# deca_pcb.net
KiCad netlist of a schematic drawn in EAGLE
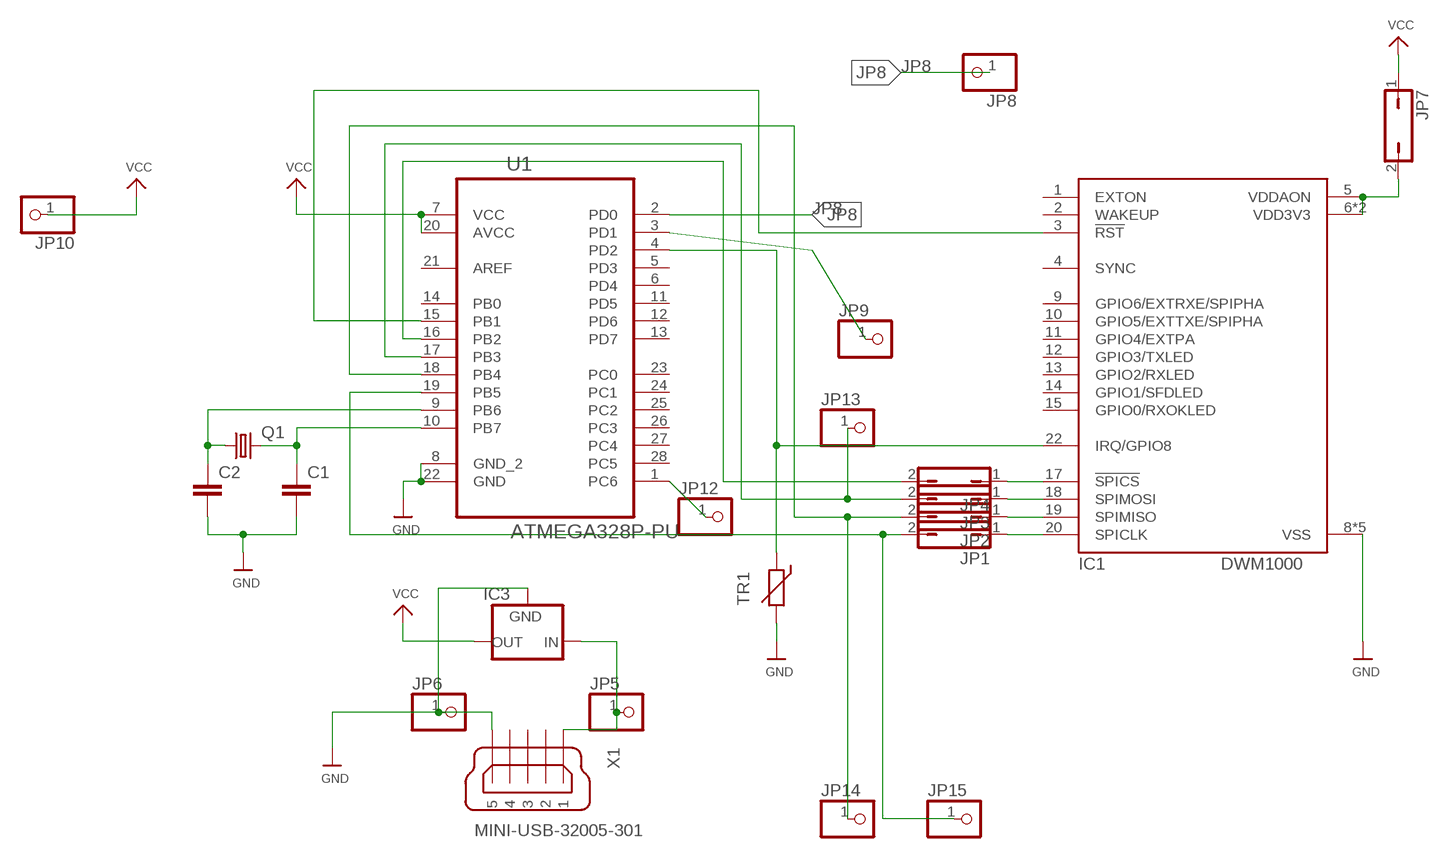
[diagram p0: schematic, sheet 1]

(export (version "E")
  (design (tool "Eeschema 10.0.6"))
  (components
    (comp (ref "C1")
      (value "C2.5/6")
      (footprint "eagle-import:C2.5-6")
      (libsource (lib "eagle-import") (part "C2.5/6"))
    )
    (comp (ref "C2")
      (value "C2.5/6")
      (footprint "eagle-import:C2.5-6")
      (libsource (lib "eagle-import") (part "C2.5/6"))
    )
    (comp (ref "IC1")
      (value "DWM1000")
      (footprint "eagle-import:DWM1000")
      (libsource (lib "eagle-import") (part "DWM1000"))
    )
    (comp (ref "IC3")
      (value "LFXXCVS")
      (footprint "eagle-import:TO220S")
      (libsource (lib "eagle-import") (part "LFXXCVS"))
    )
    (comp (ref "JP1")
      (value "JP1Q")
      (footprint "eagle-import:JP1")
      (libsource (lib "eagle-import") (part "JP1Q"))
    )
    (comp (ref "JP2")
      (value "JP1Q")
      (footprint "eagle-import:JP1")
      (libsource (lib "eagle-import") (part "JP1Q"))
    )
    (comp (ref "JP3")
      (value "JP1Q")
      (footprint "eagle-import:JP1")
      (libsource (lib "eagle-import") (part "JP1Q"))
    )
    (comp (ref "JP4")
      (value "JP1Q")
      (footprint "eagle-import:JP1")
      (libsource (lib "eagle-import") (part "JP1Q"))
    )
    (comp (ref "JP5")
      (value "PINHD-1X1_2.54")
      (footprint "eagle-import:1X01")
      (libsource (lib "eagle-import") (part "PINHD-1X1_2.54"))
    )
    (comp (ref "JP6")
      (value "PINHD-1X1_2.54")
      (footprint "eagle-import:1X01")
      (libsource (lib "eagle-import") (part "PINHD-1X1_2.54"))
    )
    (comp (ref "JP7")
      (value "JP1Q")
      (footprint "eagle-import:JP1")
      (libsource (lib "eagle-import") (part "JP1Q"))
    )
    (comp (ref "JP8")
      (value "PINHD-1X1_2.54")
      (footprint "eagle-import:1X01")
      (libsource (lib "eagle-import") (part "PINHD-1X1_2.54"))
    )
    (comp (ref "JP9")
      (value "PINHD-1X1_2.54")
      (footprint "eagle-import:1X01")
      (libsource (lib "eagle-import") (part "PINHD-1X1_2.54"))
    )
    (comp (ref "JP10")
      (value "PINHD-1X1_2.54")
      (footprint "eagle-import:1X01")
      (libsource (lib "eagle-import") (part "PINHD-1X1_2.54"))
    )
    (comp (ref "JP12")
      (value "PINHD-1X1_2.54")
      (footprint "eagle-import:1X01")
      (libsource (lib "eagle-import") (part "PINHD-1X1_2.54"))
    )
    (comp (ref "JP13")
      (value "PINHD-1X1_2.54")
      (footprint "eagle-import:1X01")
      (libsource (lib "eagle-import") (part "PINHD-1X1_2.54"))
    )
    (comp (ref "JP14")
      (value "PINHD-1X1_2.54")
      (footprint "eagle-import:1X01")
      (libsource (lib "eagle-import") (part "PINHD-1X1_2.54"))
    )
    (comp (ref "JP15")
      (value "PINHD-1X1_2.54")
      (footprint "eagle-import:1X01")
      (libsource (lib "eagle-import") (part "PINHD-1X1_2.54"))
    )
    (comp (ref "Q1")
      (value "CRYSTALHC49S")
      (footprint "eagle-import:HC49_S")
      (libsource (lib "eagle-import") (part "CRYSTALHC49S"))
    )
    (comp (ref "TR1")
      (value "THERMISTOR_R-5")
      (footprint "eagle-import:R-5")
      (libsource (lib "eagle-import") (part "THERMISTOR_R-5"))
    )
    (comp (ref "U1")
      (value "ATMEGA328P-PU")
      (footprint "eagle-import:DIP254P762X457-28")
      (libsource (lib "eagle-import") (part "ATMEGA328P-PU"))
    )
    (comp (ref "X1")
      (value "MINI-USB-32005-301")
      (footprint "eagle-import:32005-301")
      (libsource (lib "eagle-import") (part "MINI-USB-32005-301"))
    )
  )
  (nets
    (net (code "1") (name "GND") (class "Default")
      (node (ref "C1") (pin "2") (pinfunction "2_2") (pintype "passive"))
      (node (ref "C2") (pin "2") (pinfunction "2_2") (pintype "passive"))
      (node (ref "IC1") (pin "16") (pinfunction "VSS_16") (pintype "bidirectional"))
      (node (ref "IC1") (pin "21") (pinfunction "VSS_21") (pintype "bidirectional"))
      (node (ref "IC1") (pin "23") (pinfunction "VSS_23") (pintype "bidirectional"))
      (node (ref "IC1") (pin "24") (pinfunction "VSS_24") (pintype "bidirectional"))
      (node (ref "IC1") (pin "8") (pinfunction "VSS_8") (pintype "bidirectional"))
      (node (ref "IC3") (pin "2") (pinfunction "GND_2") (pintype "input"))
      (node (ref "JP6") (pin "1") (pinfunction "1_1") (pintype "passive"))
      (node (ref "TR1") (pin "2") (pinfunction "2_2") (pintype "passive"))
      (node (ref "U1") (pin "22") (pinfunction "GND_22") (pintype "passive"))
      (node (ref "U1") (pin "8") (pinfunction "GND_2_8") (pintype "passive"))
      (node (ref "X1") (pin "5") (pinfunction "5_5") (pintype "passive"))
    )
    (net (code "2") (name "JP8") (class "Default")
      (node (ref "JP8") (pin "1") (pinfunction "1_1") (pintype "passive"))
      (node (ref "U1") (pin "2") (pinfunction "PD0_2") (pintype "bidirectional"))
    )
    (net (code "3") (name "Net-(IC1-IRQ{slash}GPIO8)") (class "Default")
      (node (ref "IC1") (pin "22") (pinfunction "IRQ/GPIO8_22") (pintype "bidirectional"))
      (node (ref "TR1") (pin "1") (pinfunction "1_1") (pintype "passive"))
      (node (ref "U1") (pin "4") (pinfunction "PD2_4") (pintype "bidirectional"))
    )
    (net (code "4") (name "Net-(IC1-SPICLK)") (class "Default")
      (node (ref "IC1") (pin "20") (pinfunction "SPICLK_20") (pintype "bidirectional"))
      (node (ref "JP1") (pin "1") (pinfunction "1_1") (pintype "passive"))
    )
    (net (code "5") (name "Net-(IC1-SPIMISO)") (class "Default")
      (node (ref "IC1") (pin "19") (pinfunction "SPIMISO_19") (pintype "bidirectional"))
      (node (ref "JP2") (pin "1") (pinfunction "1_1") (pintype "passive"))
    )
    (net (code "6") (name "Net-(IC1-SPIMOSI)") (class "Default")
      (node (ref "IC1") (pin "18") (pinfunction "SPIMOSI_18") (pintype "bidirectional"))
      (node (ref "JP3") (pin "1") (pinfunction "1_1") (pintype "passive"))
    )
    (net (code "7") (name "Net-(IC1-VDDAON)") (class "Default")
      (node (ref "IC1") (pin "5") (pinfunction "VDDAON_5") (pintype "bidirectional"))
      (node (ref "IC1") (pin "6") (pinfunction "VDD3V3_6") (pintype "bidirectional"))
      (node (ref "IC1") (pin "7") (pinfunction "VDD3V3_7") (pintype "bidirectional"))
      (node (ref "JP7") (pin "2") (pinfunction "2_2") (pintype "passive"))
    )
    (net (code "8") (name "Net-(IC1-~{RST})") (class "Default")
      (node (ref "IC1") (pin "3") (pinfunction "~{RST}_3") (pintype "bidirectional"))
      (node (ref "U1") (pin "15") (pinfunction "PB1_15") (pintype "bidirectional"))
    )
    (net (code "9") (name "Net-(IC1-~{SPICS})") (class "Default")
      (node (ref "IC1") (pin "17") (pinfunction "~{SPICS}_17") (pintype "bidirectional"))
      (node (ref "JP4") (pin "1") (pinfunction "1_1") (pintype "passive"))
    )
    (net (code "10") (name "Net-(IC3-IN)") (class "Default")
      (node (ref "IC3") (pin "1") (pinfunction "IN_1") (pintype "input"))
      (node (ref "JP5") (pin "1") (pinfunction "1_1") (pintype "passive"))
      (node (ref "X1") (pin "1") (pinfunction "1_1") (pintype "passive"))
    )
    (net (code "11") (name "Net-(U1-PB2)") (class "Default")
      (node (ref "JP4") (pin "2") (pinfunction "2_2") (pintype "passive"))
      (node (ref "U1") (pin "16") (pinfunction "PB2_16") (pintype "bidirectional"))
    )
    (net (code "12") (name "Net-(U1-PB3)") (class "Default")
      (node (ref "JP13") (pin "1") (pinfunction "1_1") (pintype "passive"))
      (node (ref "JP3") (pin "2") (pinfunction "2_2") (pintype "passive"))
      (node (ref "U1") (pin "17") (pinfunction "PB3_17") (pintype "bidirectional"))
    )
    (net (code "13") (name "Net-(U1-PB4)") (class "Default")
      (node (ref "JP14") (pin "1") (pinfunction "1_1") (pintype "passive"))
      (node (ref "JP2") (pin "2") (pinfunction "2_2") (pintype "passive"))
      (node (ref "U1") (pin "18") (pinfunction "PB4_18") (pintype "bidirectional"))
    )
    (net (code "14") (name "Net-(U1-PB5)") (class "Default")
      (node (ref "JP1") (pin "2") (pinfunction "2_2") (pintype "passive"))
      (node (ref "JP15") (pin "1") (pinfunction "1_1") (pintype "passive"))
      (node (ref "U1") (pin "19") (pinfunction "PB5_19") (pintype "bidirectional"))
    )
    (net (code "15") (name "Net-(U1-PB6)") (class "Default")
      (node (ref "C2") (pin "1") (pinfunction "1_1") (pintype "passive"))
      (node (ref "Q1") (pin "1") (pinfunction "1_1") (pintype "passive"))
      (node (ref "U1") (pin "9") (pinfunction "PB6_9") (pintype "bidirectional"))
    )
    (net (code "16") (name "Net-(U1-PB7)") (class "Default")
      (node (ref "C1") (pin "1") (pinfunction "1_1") (pintype "passive"))
      (node (ref "Q1") (pin "2") (pinfunction "2_2") (pintype "passive"))
      (node (ref "U1") (pin "10") (pinfunction "PB7_10") (pintype "bidirectional"))
    )
    (net (code "17") (name "Net-(U1-PC6)") (class "Default")
      (node (ref "JP12") (pin "1") (pinfunction "1_1") (pintype "passive"))
      (node (ref "U1") (pin "1") (pinfunction "PC6_1") (pintype "bidirectional"))
    )
    (net (code "18") (name "Net-(U1-PD1)") (class "Default")
      (node (ref "JP9") (pin "1") (pinfunction "1_1") (pintype "passive"))
      (node (ref "U1") (pin "3") (pinfunction "PD1_3") (pintype "bidirectional"))
    )
    (net (code "19") (name "VCC") (class "Default")
      (node (ref "IC3") (pin "3") (pinfunction "OUT_3") (pintype "passive"))
      (node (ref "JP10") (pin "1") (pinfunction "1_1") (pintype "passive"))
      (node (ref "JP7") (pin "1") (pinfunction "1_1") (pintype "passive"))
      (node (ref "U1") (pin "20") (pinfunction "AVCC_20") (pintype "power_in"))
      (node (ref "U1") (pin "7") (pinfunction "VCC_7") (pintype "power_in"))
    )
    (net (code "20") (name "unconnected-(IC1-EXTON-Pad1)") (class "Default")
      (node (ref "IC1") (pin "1") (pinfunction "EXTON_1") (pintype "bidirectional"))
    )
    (net (code "21") (name "unconnected-(IC1-GPIO0{slash}RXOKLED-Pad15)") (class "Default")
      (node (ref "IC1") (pin "15") (pinfunction "GPIO0/RXOKLED_15") (pintype "bidirectional"))
    )
    (net (code "22") (name "unconnected-(IC1-GPIO1{slash}SFDLED-Pad14)") (class "Default")
      (node (ref "IC1") (pin "14") (pinfunction "GPIO1/SFDLED_14") (pintype "bidirectional"))
    )
    (net (code "23") (name "unconnected-(IC1-GPIO2{slash}RXLED-Pad13)") (class "Default")
      (node (ref "IC1") (pin "13") (pinfunction "GPIO2/RXLED_13") (pintype "bidirectional"))
    )
    (net (code "24") (name "unconnected-(IC1-GPIO3{slash}TXLED-Pad12)") (class "Default")
      (node (ref "IC1") (pin "12") (pinfunction "GPIO3/TXLED_12") (pintype "bidirectional"))
    )
    (net (code "25") (name "unconnected-(IC1-GPIO4{slash}EXTPA-Pad11)") (class "Default")
      (node (ref "IC1") (pin "11") (pinfunction "GPIO4/EXTPA_11") (pintype "bidirectional"))
    )
    (net (code "26") (name "unconnected-(IC1-GPIO5{slash}EXTTXE{slash}SPIPHA-Pad10)") (class "Default")
      (node (ref "IC1") (pin "10") (pinfunction "GPIO5/EXTTXE/SPIPHA_10") (pintype "bidirectional"))
    )
    (net (code "27") (name "unconnected-(IC1-GPIO6{slash}EXTRXE{slash}SPIPHA-Pad9)") (class "Default")
      (node (ref "IC1") (pin "9") (pinfunction "GPIO6/EXTRXE/SPIPHA_9") (pintype "bidirectional"))
    )
    (net (code "28") (name "unconnected-(IC1-SYNC-Pad4)") (class "Default")
      (node (ref "IC1") (pin "4") (pinfunction "SYNC_4") (pintype "bidirectional"))
    )
    (net (code "29") (name "unconnected-(IC1-WAKEUP-Pad2)") (class "Default")
      (node (ref "IC1") (pin "2") (pinfunction "WAKEUP_2") (pintype "bidirectional"))
    )
    (net (code "30") (name "unconnected-(U1-AREF-Pad21)") (class "Default")
      (node (ref "U1") (pin "21") (pinfunction "AREF_21") (pintype "input"))
    )
    (net (code "31") (name "unconnected-(U1-PB0-Pad14)") (class "Default")
      (node (ref "U1") (pin "14") (pinfunction "PB0_14") (pintype "bidirectional"))
    )
    (net (code "32") (name "unconnected-(U1-PC0-Pad23)") (class "Default")
      (node (ref "U1") (pin "23") (pinfunction "PC0_23") (pintype "bidirectional"))
    )
    (net (code "33") (name "unconnected-(U1-PC1-Pad24)") (class "Default")
      (node (ref "U1") (pin "24") (pinfunction "PC1_24") (pintype "bidirectional"))
    )
    (net (code "34") (name "unconnected-(U1-PC2-Pad25)") (class "Default")
      (node (ref "U1") (pin "25") (pinfunction "PC2_25") (pintype "bidirectional"))
    )
    (net (code "35") (name "unconnected-(U1-PC3-Pad26)") (class "Default")
      (node (ref "U1") (pin "26") (pinfunction "PC3_26") (pintype "bidirectional"))
    )
    (net (code "36") (name "unconnected-(U1-PC4-Pad27)") (class "Default")
      (node (ref "U1") (pin "27") (pinfunction "PC4_27") (pintype "bidirectional"))
    )
    (net (code "37") (name "unconnected-(U1-PC5-Pad28)") (class "Default")
      (node (ref "U1") (pin "28") (pinfunction "PC5_28") (pintype "bidirectional"))
    )
    (net (code "38") (name "unconnected-(U1-PD3-Pad5)") (class "Default")
      (node (ref "U1") (pin "5") (pinfunction "PD3_5") (pintype "bidirectional"))
    )
    (net (code "39") (name "unconnected-(U1-PD4-Pad6)") (class "Default")
      (node (ref "U1") (pin "6") (pinfunction "PD4_6") (pintype "bidirectional"))
    )
    (net (code "40") (name "unconnected-(U1-PD5-Pad11)") (class "Default")
      (node (ref "U1") (pin "11") (pinfunction "PD5_11") (pintype "bidirectional"))
    )
    (net (code "41") (name "unconnected-(U1-PD6-Pad12)") (class "Default")
      (node (ref "U1") (pin "12") (pinfunction "PD6_12") (pintype "bidirectional"))
    )
    (net (code "42") (name "unconnected-(U1-PD7-Pad13)") (class "Default")
      (node (ref "U1") (pin "13") (pinfunction "PD7_13") (pintype "bidirectional"))
    )
    (net (code "43") (name "unconnected-(X1-Pad2)") (class "Default")
      (node (ref "X1") (pin "2") (pinfunction "2_2") (pintype "passive"))
    )
    (net (code "44") (name "unconnected-(X1-Pad3)") (class "Default")
      (node (ref "X1") (pin "3") (pinfunction "3_3") (pintype "passive"))
    )
    (net (code "45") (name "unconnected-(X1-Pad4)") (class "Default")
      (node (ref "X1") (pin "4") (pinfunction "4_4") (pintype "passive"))
    )
  )
)
